# ChangeOverSwitch.net
KiCad netlist of a schematic drawn in EAGLE
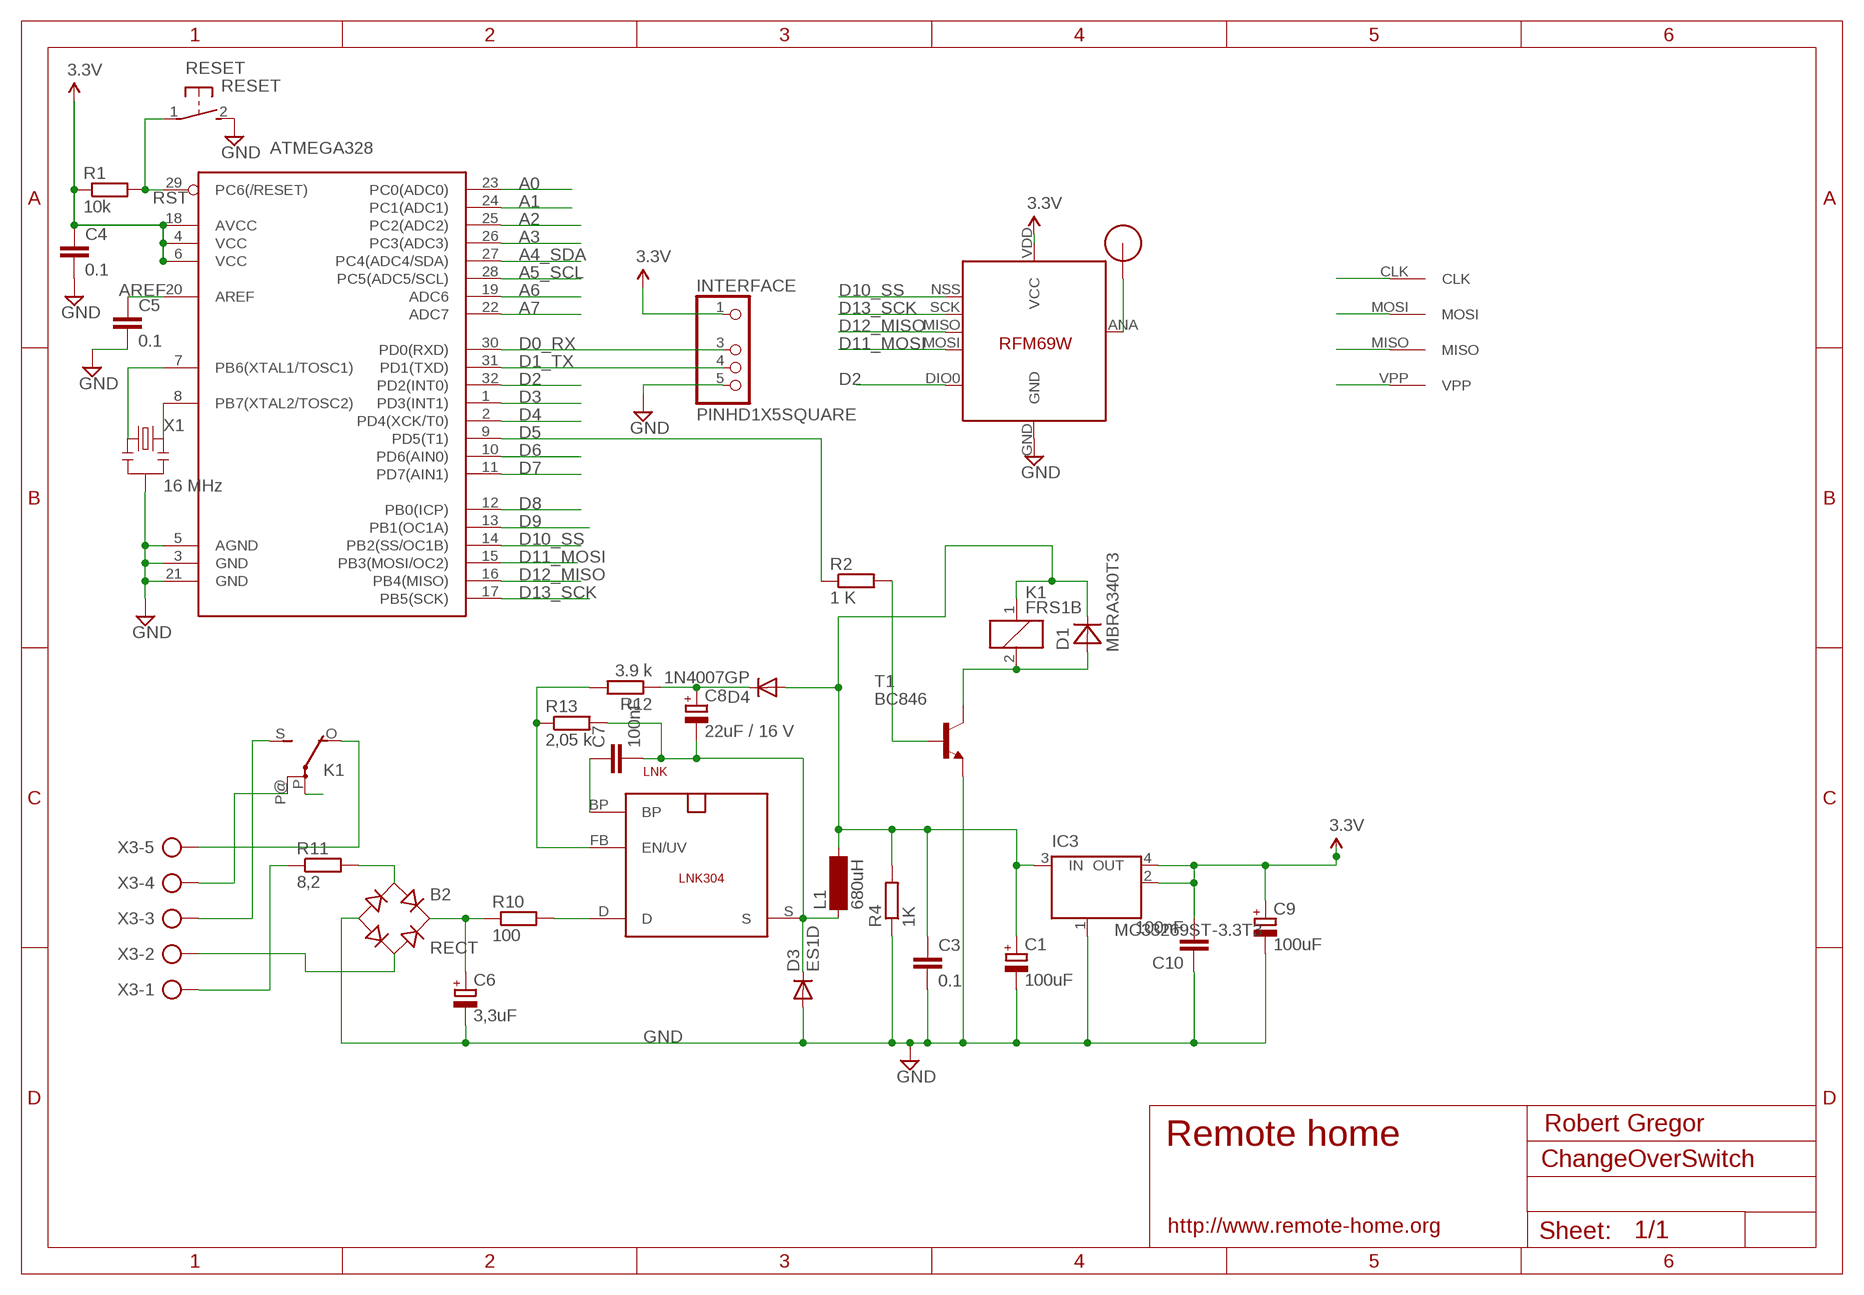
[diagram p0: schematic, sheet 1]

(export (version "E")
  (design (tool "Eeschema 10.0.6"))
  (components
    (comp (ref "ATMEGA328")
      (value "ATMega-328")
      (footprint "eagle-import:TQFP32-08")
      (libsource (lib "eagle-import") (part "ATMEGA168/328TQFP32"))
    )
    (comp (ref "B2")
      (value "RECT")
      (footprint "eagle-import:TO-269AA")
      (libsource (lib "eagle-import") (part "RECTIFIER-S40"))
    )
    (comp (ref "C1")
      (value "100uF")
      (footprint "eagle-import:SMC_B")
      (libsource (lib "eagle-import") (part "CPOL-EUSMCB"))
    )
    (comp (ref "C3")
      (value "0.1")
      (footprint "eagle-import:C2012")
      (libsource (lib "eagle-import") (part "C-EUC2012"))
    )
    (comp (ref "C4")
      (value "0.1")
      (footprint "eagle-import:C2012")
      (libsource (lib "eagle-import") (part "C-EUC2012"))
    )
    (comp (ref "C5")
      (value "0.1")
      (footprint "eagle-import:C2012")
      (libsource (lib "eagle-import") (part "C-EUC2012"))
    )
    (comp (ref "C6")
      (value "3,3uF")
      (footprint "eagle-import:E5-10,5")
      (libsource (lib "eagle-import") (part "CPOL-EUE5-10.5"))
    )
    (comp (ref "C7")
      (value "100nF")
      (footprint "eagle-import:C2012")
      (libsource (lib "eagle-import") (part "C-EUC2012"))
    )
    (comp (ref "C8")
      (value "22uF / 16 V")
      (footprint "eagle-import:SMC_C")
      (libsource (lib "eagle-import") (part "CPOL-EUSMCC"))
    )
    (comp (ref "C9")
      (value "100uF")
      (footprint "eagle-import:SMC_B")
      (libsource (lib "eagle-import") (part "CPOL-EUSMCB"))
    )
    (comp (ref "C10")
      (value "100nF")
      (footprint "eagle-import:C2012")
      (libsource (lib "eagle-import") (part "C-EUC2012"))
    )
    (comp (ref "D1")
      (value "MBRA340T3")
      (footprint "eagle-import:SMA")
      (libsource (lib "eagle-import") (part "MBRA340T3"))
    )
    (comp (ref "D3")
      (value "ES1D")
      (footprint "eagle-import:DO214AC")
      (libsource (lib "eagle-import") (part "DIODE-DO214AC"))
    )
    (comp (ref "D4")
      (value "1N4007GP")
      (footprint "eagle-import:DO214AA")
      (libsource (lib "eagle-import") (part "DIODE-DO214AA"))
    )
    (comp (ref "IC3")
      (value "MC33269ST-3.3T3")
      (footprint "eagle-import:SOT223")
      (libsource (lib "eagle-import") (part "MC33269ST-3.3T3"))
    )
    (comp (ref "INTERFACE")
      (value "PINHD1X5SQUARE")
      (footprint "eagle-import:PINHD1X05-SQUARE")
      (libsource (lib "eagle-import") (part "PINHD1X5SQUARE"))
    )
    (comp (ref "K1")
      (value "FRS1B")
      (footprint "eagle-import:FRS1B")
      (libsource (lib "eagle-import") (part "FRS1B"))
    )
    (comp (ref "L1")
      (value "680uH")
      (footprint "eagle-import:BS11")
      (libsource (lib "eagle-import") (part "BS11"))
    )
    (comp (ref "LNK")
      (value "LNK304")
      (footprint "eagle-import:SO-8C")
      (libsource (lib "eagle-import") (part "SO-8C"))
    )
    (comp (ref "R1")
      (value "10k")
      (footprint "eagle-import:R2012")
      (libsource (lib "eagle-import") (part "R-EU_R2012"))
    )
    (comp (ref "R2")
      (value "1 K")
      (footprint "eagle-import:M2012")
      (libsource (lib "eagle-import") (part "R-EU_M2012"))
    )
    (comp (ref "R4")
      (value "1K")
      (footprint "eagle-import:M2012")
      (libsource (lib "eagle-import") (part "R-EU_M2012"))
    )
    (comp (ref "R10")
      (value "100")
      (footprint "eagle-import:R2512W")
      (libsource (lib "eagle-import") (part "R-EU_R2512W"))
    )
    (comp (ref "R11")
      (value "8,2")
      (footprint "eagle-import:0411_12")
      (libsource (lib "eagle-import") (part "R-EU_0411/12"))
    )
    (comp (ref "R12")
      (value "3.9 k")
      (footprint "eagle-import:M2012")
      (libsource (lib "eagle-import") (part "R-EU_M2012"))
    )
    (comp (ref "R13")
      (value "2,05 k")
      (footprint "eagle-import:M2012")
      (libsource (lib "eagle-import") (part "R-EU_M2012"))
    )
    (comp (ref "RESET")
      (value "RESET")
      (footprint "eagle-import:DTSM-3")
      (libsource (lib "eagle-import") (part "DTSM-3"))
    )
    (comp (ref "RFM69")
      (value "RFM69")
      (footprint "eagle-import:RFM69W-MINPADS")
      (libsource (lib "eagle-import") (part "RFM69"))
    )
    (comp (ref "T1")
      (value "BC846")
      (footprint "eagle-import:SOT23")
      (libsource (lib "eagle-import") (part "BC846"))
    )
    (comp (ref "U$1")
      (value "RFM12B_ANTENNA")
      (footprint "eagle-import:RFM12B-ANTENNA")
      (libsource (lib "eagle-import") (part "RFM12B_ANTENNA"))
    )
    (comp (ref "U$2")
      (value "AVRHEADERDIP")
      (footprint "eagle-import:AVRHEADER")
      (libsource (lib "eagle-import") (part "AVRHEADERDIP"))
    )
    (comp (ref "X1")
      (value "16 MHz")
      (footprint "eagle-import:RESONATOR-SMD")
      (libsource (lib "eagle-import") (part "RESONATORSMD"))
    )
    (comp (ref "X3")
      (value "AK500/5")
      (footprint "eagle-import:AK500_5")
      (libsource (lib "eagle-import") (part "AK500/5"))
    )
  )
  (nets
    (net (code "1") (name "/A0") (class "Default")
      (node (ref "ATMEGA328") (pin "23") (pinfunction "PC0(ADC0)_23") (pintype "bidirectional"))
    )
    (net (code "2") (name "/A1") (class "Default")
      (node (ref "ATMEGA328") (pin "24") (pinfunction "PC1(ADC1)_24") (pintype "bidirectional"))
    )
    (net (code "3") (name "/A2") (class "Default")
      (node (ref "ATMEGA328") (pin "25") (pinfunction "PC2(ADC2)_25") (pintype "bidirectional"))
    )
    (net (code "4") (name "/A3") (class "Default")
      (node (ref "ATMEGA328") (pin "26") (pinfunction "PC3(ADC3)_26") (pintype "bidirectional"))
    )
    (net (code "5") (name "/A4_SDA") (class "Default")
      (node (ref "ATMEGA328") (pin "27") (pinfunction "PC4(ADC4/SDA)_27") (pintype "bidirectional"))
    )
    (net (code "6") (name "/A5_SCL") (class "Default")
      (node (ref "ATMEGA328") (pin "28") (pinfunction "PC5(ADC5/SCL)_28") (pintype "bidirectional"))
    )
    (net (code "7") (name "/A6") (class "Default")
      (node (ref "ATMEGA328") (pin "19") (pinfunction "ADC6_19") (pintype "bidirectional"))
    )
    (net (code "8") (name "/A7") (class "Default")
      (node (ref "ATMEGA328") (pin "22") (pinfunction "ADC7_22") (pintype "bidirectional"))
    )
    (net (code "9") (name "/AREF") (class "Default")
      (node (ref "ATMEGA328") (pin "20") (pinfunction "AREF_20") (pintype "bidirectional"))
      (node (ref "C5") (pin "1") (pinfunction "1_1") (pintype "passive"))
    )
    (net (code "10") (name "/D0_RX") (class "Default")
      (node (ref "ATMEGA328") (pin "30") (pinfunction "PD0(RXD)_30") (pintype "bidirectional"))
      (node (ref "INTERFACE") (pin "3") (pinfunction "3_3") (pintype "passive"))
    )
    (net (code "11") (name "/D1_TX") (class "Default")
      (node (ref "ATMEGA328") (pin "31") (pinfunction "PD1(TXD)_31") (pintype "bidirectional"))
      (node (ref "INTERFACE") (pin "4") (pinfunction "4_4") (pintype "passive"))
    )
    (net (code "12") (name "/D2") (class "Default")
      (node (ref "ATMEGA328") (pin "32") (pinfunction "PD2(INT0)_32") (pintype "bidirectional"))
      (node (ref "RFM69") (pin "DIO0") (pinfunction "DIO0_DIO0") (pintype "open_collector"))
    )
    (net (code "13") (name "/D3") (class "Default")
      (node (ref "ATMEGA328") (pin "1") (pinfunction "PD3(INT1)_1") (pintype "bidirectional"))
    )
    (net (code "14") (name "/D4") (class "Default")
      (node (ref "ATMEGA328") (pin "2") (pinfunction "PD4(XCK/T0)_2") (pintype "bidirectional"))
    )
    (net (code "15") (name "/D5") (class "Default")
      (node (ref "ATMEGA328") (pin "9") (pinfunction "PD5(T1)_9") (pintype "bidirectional"))
      (node (ref "R2") (pin "1") (pinfunction "1_1") (pintype "passive"))
    )
    (net (code "16") (name "/D6") (class "Default")
      (node (ref "ATMEGA328") (pin "10") (pinfunction "PD6(AIN0)_10") (pintype "bidirectional"))
    )
    (net (code "17") (name "/D7") (class "Default")
      (node (ref "ATMEGA328") (pin "11") (pinfunction "PD7(AIN1)_11") (pintype "bidirectional"))
    )
    (net (code "18") (name "/D8") (class "Default")
      (node (ref "ATMEGA328") (pin "12") (pinfunction "PB0(ICP)_12") (pintype "bidirectional"))
    )
    (net (code "19") (name "/D9") (class "Default")
      (node (ref "ATMEGA328") (pin "13") (pinfunction "PB1(OC1A)_13") (pintype "bidirectional"))
    )
    (net (code "20") (name "/D10_SS") (class "Default")
      (node (ref "ATMEGA328") (pin "14") (pinfunction "PB2(SS/OC1B)_14") (pintype "bidirectional"))
      (node (ref "RFM69") (pin "NSS") (pinfunction "SEL_NSS") (pintype "input"))
    )
    (net (code "21") (name "/D11_MOSI") (class "Default")
      (node (ref "ATMEGA328") (pin "15") (pinfunction "PB3(MOSI/OC2)_15") (pintype "bidirectional"))
      (node (ref "RFM69") (pin "MOSI") (pinfunction "MOSI_MOSI") (pintype "output"))
      (node (ref "U$2") (pin "MOSI") (pinfunction "MOSI_MOSI") (pintype "bidirectional"))
    )
    (net (code "22") (name "/D12_MISO") (class "Default")
      (node (ref "ATMEGA328") (pin "16") (pinfunction "PB4(MISO)_16") (pintype "bidirectional"))
      (node (ref "RFM69") (pin "MISO") (pinfunction "MISO_MISO") (pintype "input"))
      (node (ref "U$2") (pin "MISO") (pinfunction "MISO_MISO") (pintype "bidirectional"))
    )
    (net (code "23") (name "/D13_SCK") (class "Default")
      (node (ref "ATMEGA328") (pin "17") (pinfunction "PB5(SCK)_17") (pintype "bidirectional"))
      (node (ref "RFM69") (pin "SCK") (pinfunction "SCK_SCK") (pintype "input"))
      (node (ref "U$2") (pin "CLK") (pinfunction "CLK_CLK") (pintype "bidirectional"))
    )
    (net (code "24") (name "/RST") (class "Default")
      (node (ref "ATMEGA328") (pin "29") (pinfunction "PC6(/RESET)_29") (pintype "bidirectional"))
      (node (ref "R1") (pin "2") (pinfunction "2_2") (pintype "passive"))
      (node (ref "RESET") (pin "1") (pinfunction "1_1") (pintype "passive"))
      (node (ref "U$2") (pin "VPP") (pinfunction "VPP_VPP") (pintype "bidirectional"))
    )
    (net (code "25") (name "3.3V") (class "Default")
      (node (ref "ATMEGA328") (pin "18") (pinfunction "AVCC_18") (pintype "bidirectional"))
      (node (ref "ATMEGA328") (pin "4") (pinfunction "VCC_4") (pintype "bidirectional"))
      (node (ref "ATMEGA328") (pin "6") (pinfunction "VCC_6") (pintype "bidirectional"))
      (node (ref "C10") (pin "2") (pinfunction "2_2") (pintype "passive"))
      (node (ref "C4") (pin "1") (pinfunction "1_1") (pintype "passive"))
      (node (ref "C9") (pin "+") (pinfunction "+_+") (pintype "passive"))
      (node (ref "IC3") (pin "2") (pinfunction "OUT_2") (pintype "passive"))
      (node (ref "IC3") (pin "4") (pinfunction "OUT_4") (pintype "passive"))
      (node (ref "INTERFACE") (pin "1") (pinfunction "1_1") (pintype "passive"))
      (node (ref "R1") (pin "1") (pinfunction "1_1") (pintype "passive"))
      (node (ref "RFM69") (pin "VDD") (pinfunction "VCC_VDD") (pintype "power_in"))
    )
    (net (code "26") (name "GND") (class "Default")
      (node (ref "ATMEGA328") (pin "21") (pinfunction "GND_21") (pintype "bidirectional"))
      (node (ref "ATMEGA328") (pin "3") (pinfunction "GND_3") (pintype "bidirectional"))
      (node (ref "ATMEGA328") (pin "5") (pinfunction "AGND_5") (pintype "bidirectional"))
      (node (ref "B2") (pin "-") (pinfunction "-_-") (pintype "passive"))
      (node (ref "C1") (pin "-") (pinfunction "-_-") (pintype "passive"))
      (node (ref "C10") (pin "1") (pinfunction "1_1") (pintype "passive"))
      (node (ref "C3") (pin "2") (pinfunction "2_2") (pintype "passive"))
      (node (ref "C4") (pin "2") (pinfunction "2_2") (pintype "passive"))
      (node (ref "C5") (pin "2") (pinfunction "2_2") (pintype "passive"))
      (node (ref "C6") (pin "-") (pinfunction "-_-") (pintype "passive"))
      (node (ref "C9") (pin "-") (pinfunction "-_-") (pintype "passive"))
      (node (ref "D3") (pin "A") (pinfunction "A_A") (pintype "passive"))
      (node (ref "IC3") (pin "1") (pinfunction "GND/ADJ_1") (pintype "input"))
      (node (ref "INTERFACE") (pin "5") (pinfunction "5_5") (pintype "passive"))
      (node (ref "R4") (pin "1") (pinfunction "1_1") (pintype "passive"))
      (node (ref "RESET") (pin "2") (pinfunction "2_2") (pintype "passive"))
      (node (ref "RFM69") (pin "GND") (pinfunction "GND_GND") (pintype "power_in"))
      (node (ref "T1") (pin "2") (pinfunction "E_2") (pintype "passive"))
      (node (ref "X1") (pin "2") (pinfunction "2_2") (pintype "passive"))
    )
    (net (code "27") (name "Net-(ATMEGA328-PB6(XTAL1{slash}TOSC1))") (class "Default")
      (node (ref "ATMEGA328") (pin "7") (pinfunction "PB6(XTAL1/TOSC1)_7") (pintype "bidirectional"))
      (node (ref "X1") (pin "1") (pinfunction "1_1") (pintype "passive"))
    )
    (net (code "28") (name "Net-(ATMEGA328-PB7(XTAL2{slash}TOSC2))") (class "Default")
      (node (ref "ATMEGA328") (pin "8") (pinfunction "PB7(XTAL2/TOSC2)_8") (pintype "bidirectional"))
      (node (ref "X1") (pin "3") (pinfunction "3_3") (pintype "passive"))
    )
    (net (code "29") (name "Net-(B2-Pad+)") (class "Default")
      (node (ref "B2") (pin "+") (pinfunction "+_+") (pintype "passive"))
      (node (ref "C6") (pin "+") (pinfunction "+_+") (pintype "passive"))
      (node (ref "R10") (pin "1") (pinfunction "1_1") (pintype "passive"))
    )
    (net (code "30") (name "Net-(B2-PadAC1)") (class "Default")
      (node (ref "B2") (pin "AC1") (pinfunction "AC1_AC1") (pintype "passive"))
      (node (ref "R11") (pin "2") (pinfunction "2_2") (pintype "passive"))
    )
    (net (code "31") (name "Net-(C7-Pad1)") (class "Default")
      (node (ref "C7") (pin "1") (pinfunction "1_1") (pintype "passive"))
      (node (ref "LNK") (pin "BP") (pinfunction "BP_BP") (pintype "passive"))
    )
    (net (code "32") (name "Net-(C7-Pad2)") (class "Default")
      (node (ref "C7") (pin "2") (pinfunction "2_2") (pintype "passive"))
      (node (ref "C8") (pin "-") (pinfunction "-_-") (pintype "passive"))
      (node (ref "D3") (pin "C") (pinfunction "C_C") (pintype "passive"))
      (node (ref "L1") (pin "1") (pinfunction "1_1") (pintype "passive"))
      (node (ref "LNK") (pin "S") (pinfunction "S_S") (pintype "power_in"))
      (node (ref "R13") (pin "2") (pinfunction "2_2") (pintype "passive"))
    )
    (net (code "33") (name "Net-(C8-Pad+)") (class "Default")
      (node (ref "C8") (pin "+") (pinfunction "+_+") (pintype "passive"))
      (node (ref "D4") (pin "C") (pinfunction "C_C") (pintype "passive"))
      (node (ref "R12") (pin "1") (pinfunction "1_1") (pintype "passive"))
    )
    (net (code "34") (name "Net-(IC3-IN)") (class "Default")
      (node (ref "C1") (pin "+") (pinfunction "+_+") (pintype "passive"))
      (node (ref "C3") (pin "1") (pinfunction "1_1") (pintype "passive"))
      (node (ref "D1") (pin "C") (pinfunction "C_C") (pintype "passive"))
      (node (ref "D4") (pin "A") (pinfunction "A_A") (pintype "passive"))
      (node (ref "IC3") (pin "3") (pinfunction "IN_3") (pintype "input"))
      (node (ref "K1") (pin "1") (pinfunction "1_1") (pintype "passive"))
      (node (ref "L1") (pin "2") (pinfunction "2_2") (pintype "passive"))
      (node (ref "R4") (pin "2") (pinfunction "2_2") (pintype "passive"))
    )
    (net (code "35") (name "Net-(LNK-EN{slash}UV)") (class "Default")
      (node (ref "LNK") (pin "FB") (pinfunction "EN/UV_FB") (pintype "input"))
      (node (ref "R12") (pin "2") (pinfunction "2_2") (pintype "passive"))
      (node (ref "R13") (pin "1") (pinfunction "1_1") (pintype "passive"))
    )
    (net (code "36") (name "Net-(LNK-PadD)") (class "Default")
      (node (ref "LNK") (pin "D") (pinfunction "D_D") (pintype "open_collector"))
      (node (ref "R10") (pin "2") (pinfunction "2_2") (pintype "passive"))
    )
    (net (code "37") (name "Net-(RFM69-ANT)") (class "Default")
      (node (ref "RFM69") (pin "ANA") (pinfunction "ANT_ANA") (pintype "passive"))
      (node (ref "U$1") (pin "P$1") (pinfunction "1_P$1") (pintype "bidirectional"))
    )
    (net (code "38") (name "Net-(T1-B)") (class "Default")
      (node (ref "R2") (pin "2") (pinfunction "2_2") (pintype "passive"))
      (node (ref "T1") (pin "1") (pinfunction "B_1") (pintype "passive"))
    )
    (net (code "39") (name "Net-(T1-C)") (class "Default")
      (node (ref "D1") (pin "A") (pinfunction "A_A") (pintype "passive"))
      (node (ref "K1") (pin "2") (pinfunction "2_2") (pintype "passive"))
      (node (ref "T1") (pin "3") (pinfunction "C_3") (pintype "passive"))
    )
    (net (code "40") (name "Net-(X3A-KL)") (class "Default")
      (node (ref "R11") (pin "1") (pinfunction "1_1") (pintype "passive"))
      (node (ref "X3") (pin "1") (pinfunction "KL_1") (pintype "passive"))
    )
    (net (code "41") (name "Net-(X3B-KL)") (class "Default")
      (node (ref "B2") (pin "AC2") (pinfunction "AC2_AC2") (pintype "passive"))
      (node (ref "X3") (pin "2") (pinfunction "KL_2") (pintype "passive"))
    )
    (net (code "42") (name "Net-(X3C-KL)") (class "Default")
      (node (ref "K1") (pin "S") (pinfunction "S_S") (pintype "passive"))
      (node (ref "X3") (pin "3") (pinfunction "KL_3") (pintype "passive"))
    )
    (net (code "43") (name "Net-(X3D-KL)") (class "Default")
      (node (ref "K1") (pin "P@") (pinfunction "P_P@") (pintype "passive"))
      (node (ref "X3") (pin "4") (pinfunction "KL_4") (pintype "passive"))
    )
    (net (code "44") (name "Net-(X3E-KL)") (class "Default")
      (node (ref "K1") (pin "O") (pinfunction "O_O") (pintype "passive"))
      (node (ref "X3") (pin "5") (pinfunction "KL_5") (pintype "passive"))
    )
    (net (code "45") (name "unconnected-(K1-PadP)") (class "Default")
      (node (ref "K1") (pin "P") (pinfunction "P_P") (pintype "passive"))
    )
  )
)
